# io_a.net
KiCad netlist of a schematic drawn in Altium Designer
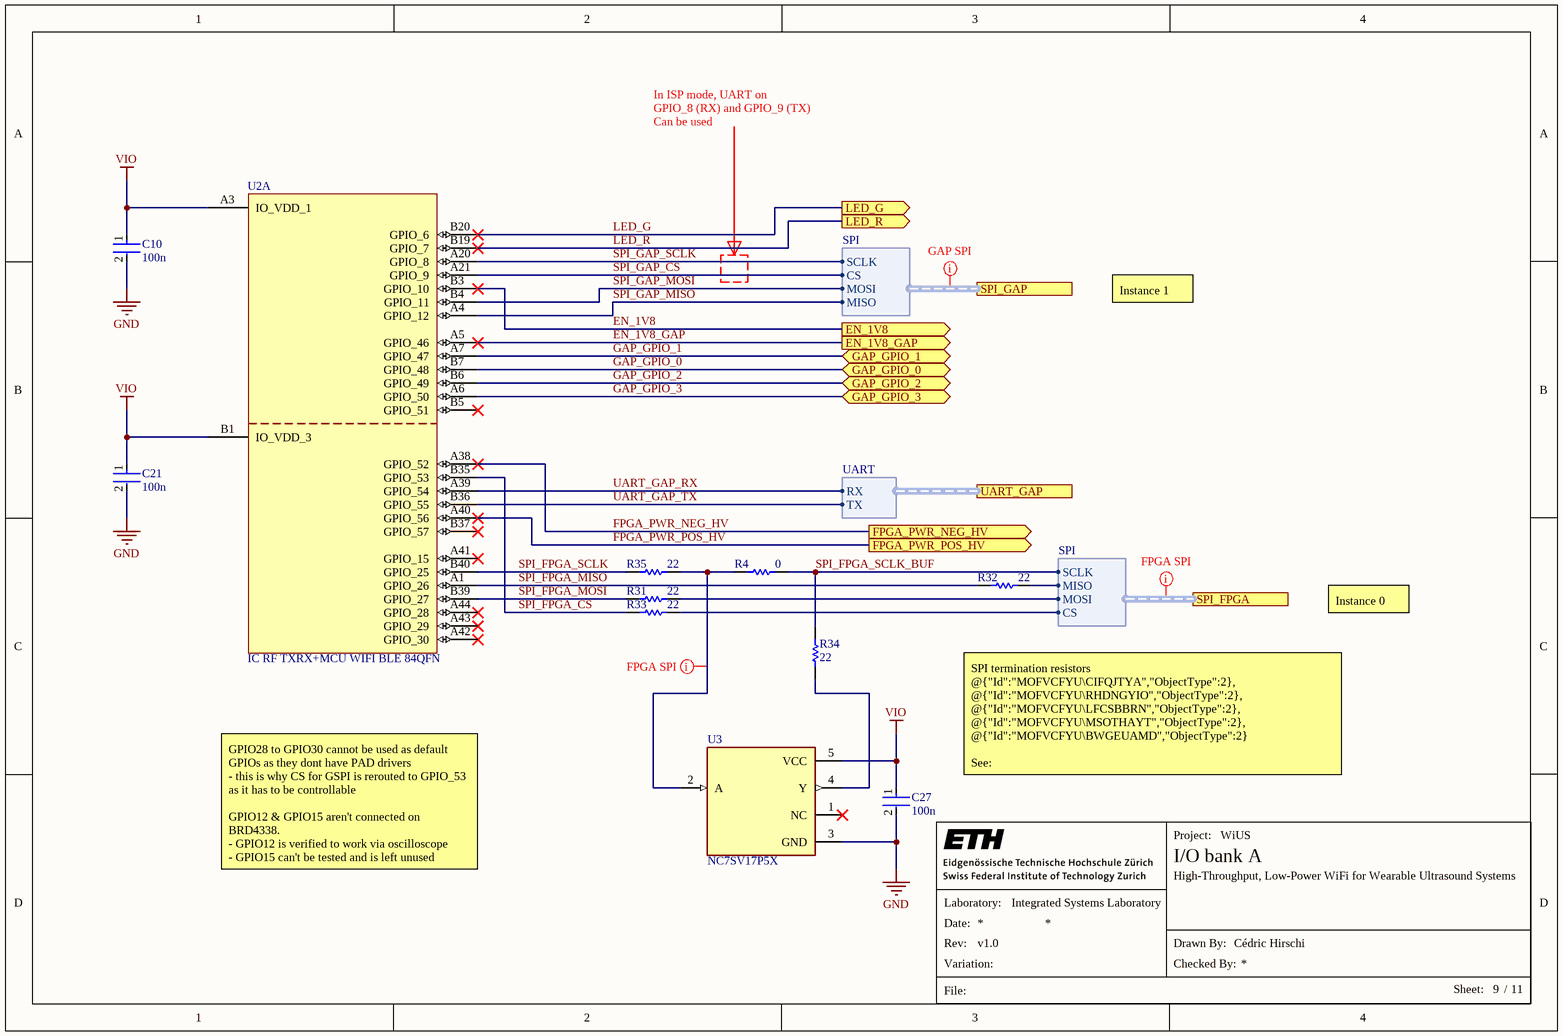
[diagram p0: io_a.SchDoc]

(export (version "E")
  (design (tool "Eeschema 10.0.6"))
  (components
    (comp (ref "C10")
      (value "100n")
      (footprint "FP-GRT155-0_05-MFG")
      (description "Multi-Layer Ceramic Capacitor 100nF 50V X7R ±10% 0402 Paper T/R")
      (libsource (lib "Altium Content Vault") (part "02cd4be3c70576c341d710602a673aa"))
    )
    (comp (ref "C21")
      (value "100n")
      (footprint "FP-GRT155-0_05-MFG")
      (description "Multi-Layer Ceramic Capacitor 100nF 50V X7R ±10% 0402 Paper T/R")
      (libsource (lib "Altium Content Vault") (part "02cd4be3c70576c341d710602a673aa"))
    )
    (comp (ref "C27")
      (value "100n")
      (footprint "FP-GRT155-0_05-MFG")
      (description "Multi-Layer Ceramic Capacitor 100nF 50V X7R ±10% 0402 Paper T/R")
      (libsource (lib "Altium Content Vault") (part "02cd4be3c70576c341d710602a673aa"))
    )
    (comp (ref "R4")
      (value "0")
      (footprint "RESC1005X40X25ML05T10")
      (description "Chip Resistor, 0 Ohm, 0.063 W, -55 to 155 degC, 0402 (1005 Metric)")
      (fields (field (name "POWER") "63mW") (field (name "Comment") "Resistor 0R 0402 63 mW"))
      (libsource (lib "Cédric's Workspace") (part "RES-2"))
    )
    (comp (ref "R31")
      (value "22")
      (footprint "RESC1005X40X25LL05T10")
      (fields (field (name "MANUFACTURER") "Yageo / Phycomp") (field (name "PART NUMBER") "RC0402FR-0722RL"))
      (libsource (lib "Altium Content Vault") (part "RES"))
    )
    (comp (ref "R32")
      (value "22")
      (footprint "RESC1005X40X25LL05T10")
      (fields (field (name "MANUFACTURER") "Yageo / Phycomp") (field (name "PART NUMBER") "RC0402FR-0722RL"))
      (libsource (lib "Altium Content Vault") (part "RES"))
    )
    (comp (ref "R33")
      (value "22")
      (footprint "RESC1005X40X25LL05T10")
      (fields (field (name "MANUFACTURER") "Yageo / Phycomp") (field (name "PART NUMBER") "RC0402FR-0722RL"))
      (libsource (lib "Altium Content Vault") (part "RES"))
    )
    (comp (ref "R34")
      (value "22")
      (footprint "RESC1005X40X25LL05T10")
      (fields (field (name "MANUFACTURER") "Yageo / Phycomp") (field (name "PART NUMBER") "RC0402FR-0722RL"))
      (libsource (lib "Altium Content Vault") (part "RES"))
    )
    (comp (ref "R35")
      (value "22")
      (footprint "RESC1005X40X25LL05T10")
      (fields (field (name "MANUFACTURER") "Yageo / Phycomp") (field (name "PART NUMBER") "RC0402FR-0722RL"))
      (libsource (lib "Altium Content Vault") (part "RES"))
    )
    (comp (ref "U2")
      (value "IC RF TXRX+MCU WIFI BLE 84QFN")
      (footprint "wius:SIWG917M110LGTBA")
      (libsource (lib "wius") (part "SIWG917"))
    )
    (comp (ref "U3")
      (value "NC7SV17P5X")
      (footprint "wius:SOT65P210X110-5N")
      (description "Buffer, Non-Inverting 1 Element 1 Bit per Element Push-Pull Output SC-70-5")
      (fields (field (name "MF") "{'manufacturer': u'ON Semiconductor'}"))
      (libsource (lib "wius") (part "NC7SV17P5X"))
    )
  )
  (nets
    (net (code "3") (name "/EN_1V8") (class "Default")
      (node (ref "U2") (pin "B3") (pinfunction "GPIO_10_B3") (pintype "bidirectional+no_connect"))
    )
    (net (code "4") (name "/EN_1V8_GAP") (class "Default")
      (node (ref "U2") (pin "A5") (pinfunction "GPIO_46_A5") (pintype "bidirectional+no_connect"))
    )
    (net (code "5") (name "/FPGA_PWR_NEG_HV") (class "Default")
      (node (ref "U2") (pin "A38") (pinfunction "GPIO_52_A38") (pintype "bidirectional+no_connect"))
    )
    (net (code "6") (name "/FPGA_PWR_POS_HV") (class "Default")
      (node (ref "U2") (pin "A40") (pinfunction "GPIO_56_A40") (pintype "bidirectional+no_connect"))
    )
    (net (code "7") (name "/GAP_GPIO_0") (class "Default")
      (node (ref "U2") (pin "B7") (pinfunction "GPIO_48_B7") (pintype "bidirectional"))
    )
    (net (code "8") (name "/GAP_GPIO_1") (class "Default")
      (node (ref "U2") (pin "A7") (pinfunction "GPIO_47_A7") (pintype "bidirectional"))
    )
    (net (code "9") (name "/GAP_GPIO_2") (class "Default")
      (node (ref "U2") (pin "B6") (pinfunction "GPIO_49_B6") (pintype "bidirectional"))
    )
    (net (code "10") (name "/GAP_GPIO_3") (class "Default")
      (node (ref "U2") (pin "A6") (pinfunction "GPIO_50_A6") (pintype "bidirectional"))
    )
    (net (code "11") (name "/LED_G") (class "Default")
      (node (ref "U2") (pin "B20") (pinfunction "GPIO_6_B20") (pintype "bidirectional+no_connect"))
    )
    (net (code "12") (name "/LED_R") (class "Default")
      (node (ref "U2") (pin "B19") (pinfunction "GPIO_7_B19") (pintype "bidirectional+no_connect"))
    )
    (net (code "13") (name "/SPI_FPGA_CS") (class "Default")
      (node (ref "R33") (pin "1") (pinfunction "1_1") (pintype "passive"))
      (node (ref "U2") (pin "B35") (pinfunction "GPIO_53_B35") (pintype "bidirectional"))
    )
    (net (code "14") (name "/SPI_FPGA_MISO") (class "Default")
      (node (ref "R32") (pin "1") (pinfunction "1_1") (pintype "passive"))
      (node (ref "U2") (pin "A1") (pinfunction "GPIO_26_A1") (pintype "bidirectional"))
    )
    (net (code "15") (name "/SPI_FPGA_MOSI") (class "Default")
      (node (ref "R31") (pin "1") (pinfunction "1_1") (pintype "passive"))
      (node (ref "U2") (pin "B39") (pinfunction "GPIO_27_B39") (pintype "bidirectional"))
    )
    (net (code "16") (name "/SPI_FPGA_SCLK") (class "Default")
      (node (ref "R35") (pin "1") (pinfunction "1_1") (pintype "passive"))
      (node (ref "U2") (pin "B40") (pinfunction "GPIO_25_B40") (pintype "bidirectional"))
    )
    (net (code "17") (name "/SPI_FPGA_SCLK_BUF") (class "Default")
      (node (ref "R34") (pin "2") (pinfunction "2_2") (pintype "passive"))
      (node (ref "R4") (pin "2") (pinfunction "2_2") (pintype "passive"))
    )
    (net (code "18") (name "/SPI_GAP_CS") (class "Default")
      (node (ref "U2") (pin "A21") (pinfunction "GPIO_9_A21") (pintype "bidirectional"))
    )
    (net (code "19") (name "/SPI_GAP_MISO") (class "Default")
      (node (ref "U2") (pin "A4") (pinfunction "GPIO_12_A4") (pintype "bidirectional"))
    )
    (net (code "20") (name "/SPI_GAP_MOSI") (class "Default")
      (node (ref "U2") (pin "B4") (pinfunction "GPIO_11_B4") (pintype "bidirectional"))
    )
    (net (code "21") (name "/SPI_GAP_SCLK") (class "Default")
      (node (ref "U2") (pin "A20") (pinfunction "GPIO_8_A20") (pintype "bidirectional"))
    )
    (net (code "22") (name "/UART_GAP_RX") (class "Default")
      (node (ref "U2") (pin "A39") (pinfunction "GPIO_54_A39") (pintype "bidirectional"))
    )
    (net (code "23") (name "/UART_GAP_TX") (class "Default")
      (node (ref "U2") (pin "B36") (pinfunction "GPIO_55_B36") (pintype "bidirectional"))
    )
    (net (code "26") (name "GND") (class "Default")
      (node (ref "C10") (pin "2") (pinfunction "2_2") (pintype "passive"))
      (node (ref "C21") (pin "2") (pinfunction "2_2") (pintype "passive"))
      (node (ref "C27") (pin "2") (pinfunction "2_2") (pintype "passive"))
      (node (ref "U3") (pin "3") (pinfunction "GND_3") (pintype "power_in"))
    )
    (net (code "27") (name "Net-(U3-A)") (class "Default")
      (node (ref "R35") (pin "2") (pinfunction "2_2") (pintype "passive"))
      (node (ref "R4") (pin "1") (pinfunction "1_1") (pintype "passive"))
      (node (ref "U3") (pin "2") (pinfunction "A_2") (pintype "input"))
    )
    (net (code "28") (name "Net-(U3-Y)") (class "Default")
      (node (ref "R34") (pin "1") (pinfunction "1_1") (pintype "passive"))
      (node (ref "U3") (pin "4") (pinfunction "Y_4") (pintype "output"))
    )
    (net (code "29") (name "VIO") (class "Default")
      (node (ref "C10") (pin "1") (pinfunction "1_1") (pintype "passive"))
      (node (ref "C21") (pin "1") (pinfunction "1_1") (pintype "passive"))
      (node (ref "C27") (pin "1") (pinfunction "1_1") (pintype "passive"))
      (node (ref "U2") (pin "A3") (pinfunction "IO_VDD_1_A3") (pintype "power_in"))
      (node (ref "U2") (pin "B1") (pinfunction "IO_VDD_3_B1") (pintype "power_in"))
      (node (ref "U3") (pin "5") (pinfunction "VCC_5") (pintype "power_in"))
    )
    (net (code "30") (name "unconnected-(R31-Pad2)") (class "Default")
      (node (ref "R31") (pin "2") (pinfunction "2_2") (pintype "passive"))
    )
    (net (code "31") (name "unconnected-(R32-Pad2)") (class "Default")
      (node (ref "R32") (pin "2") (pinfunction "2_2") (pintype "passive"))
    )
    (net (code "32") (name "unconnected-(R33-Pad2)") (class "Default")
      (node (ref "R33") (pin "2") (pinfunction "2_2") (pintype "passive"))
    )
    (net (code "33") (name "unconnected-(U2A-GPIO_15-PadA41)") (class "Default")
      (node (ref "U2") (pin "A41") (pinfunction "GPIO_15_A41") (pintype "bidirectional+no_connect"))
    )
    (net (code "34") (name "unconnected-(U2A-GPIO_28-PadA44)") (class "Default")
      (node (ref "U2") (pin "A44") (pinfunction "GPIO_28_A44") (pintype "bidirectional+no_connect"))
    )
    (net (code "35") (name "unconnected-(U2A-GPIO_29-PadA43)") (class "Default")
      (node (ref "U2") (pin "A43") (pinfunction "GPIO_29_A43") (pintype "bidirectional+no_connect"))
    )
    (net (code "36") (name "unconnected-(U2A-GPIO_30-PadA42)") (class "Default")
      (node (ref "U2") (pin "A42") (pinfunction "GPIO_30_A42") (pintype "bidirectional+no_connect"))
    )
    (net (code "37") (name "unconnected-(U2A-GPIO_51-PadB5)") (class "Default")
      (node (ref "U2") (pin "B5") (pinfunction "GPIO_51_B5") (pintype "bidirectional+no_connect"))
    )
    (net (code "38") (name "unconnected-(U2A-GPIO_57-PadB37)") (class "Default")
      (node (ref "U2") (pin "B37") (pinfunction "GPIO_57_B37") (pintype "bidirectional+no_connect"))
    )
    (net (code "39") (name "unconnected-(U3-NC-Pad1)") (class "Default")
      (node (ref "U3") (pin "1") (pinfunction "NC_1") (pintype "passive+no_connect"))
    )
  )
)
